# PWR_1117.net
KiCad netlist of a schematic drawn in Altium Designer
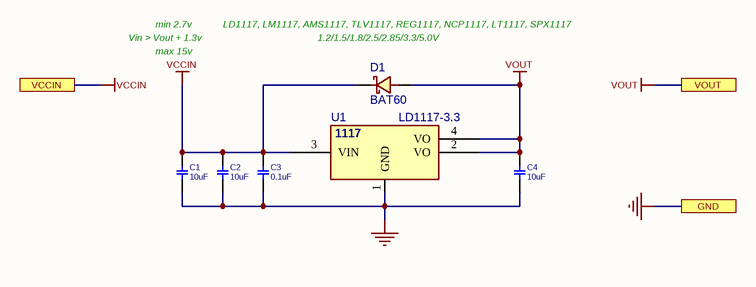
[diagram p0: PWR_1117.SchDoc]

(export (version "E")
  (design (tool "Eeschema 10.0.6"))
  (components
    (comp (ref "C1")
      (value "10uF")
      (footprint "C0805")
      (description "CAP, MLCC, -F, -V, MATERIAL, -%, 1206")
      (fields (field (name "MANF_P#") "MANF_PART#"))
      (libsource (lib "passive_smd") (part "CAP_SMD_MLCC_1206"))
    )
    (comp (ref "C2")
      (value "10uF")
      (footprint "C0805")
      (description "CAP, MLCC, -F, -V, MATERIAL, -%, 1206")
      (fields (field (name "MANF_P#") "MANF_PART#"))
      (libsource (lib "passive_smd") (part "CAP_SMD_MLCC_1206"))
    )
    (comp (ref "C3")
      (value "0.1uF")
      (footprint "C0603")
      (description "CAP, MLCC, -F, -V, MATERIAL, -%, 0805")
      (fields (field (name "MANF_P#") "MANF_PART#"))
      (libsource (lib "passive_smd") (part "CAP_SMD_MLCC_0805"))
    )
    (comp (ref "C4")
      (value "10uF")
      (footprint "C0805")
      (description "CAP, MLCC, -F, -V, MATERIAL, -%, 1206")
      (fields (field (name "MANF_P#") "MANF_PART#"))
      (libsource (lib "passive_smd") (part "CAP_SMD_MLCC_1206"))
    )
    (comp (ref "D1")
      (value "BAT60")
      (footprint "D_SOD323")
      (description "DIODE, SCHOTTKY, 10V, 3A, 0.3Vf")
      (fields (field (name "MANF") "Infineon") (field (name "MANF_P#") "BAT60AE6327HTSA1"))
      (libsource (lib "diode") (part "DIODE_SMD_SCHOTTKY_BAT60"))
    )
    (comp (ref "U1")
      (value "LD1117-3.3")
      (footprint "SOT223_4")
      (description "REG, Linear, LDO1V, 0.8A, SOT-223")
      (fields
        (field (name "MANF_P#") "LD1117, LM1117, AMS1117, TLV1117, REG1117, NCP1117, LT1117, SPX1117")
        (field (name "MANF") "TI, ON, ST")
      )
      (libsource (lib "pwr_reg_linear_1117") (part "VREG_1117_SOT223"))
    )
  )
  (nets
    (net (code "1") (name "GND") (class "Default")
      (node (ref "C1") (pin "2") (pinfunction "2_2") (pintype "passive"))
      (node (ref "C2") (pin "2") (pinfunction "2_2") (pintype "passive"))
      (node (ref "C3") (pin "1") (pinfunction "1_1") (pintype "passive"))
      (node (ref "C4") (pin "2") (pinfunction "2_2") (pintype "passive"))
      (node (ref "U1") (pin "1") (pinfunction "GND_1") (pintype "passive"))
    )
    (net (code "2") (name "VCCIN") (class "Default")
      (node (ref "C1") (pin "1") (pinfunction "1_1") (pintype "passive"))
      (node (ref "C2") (pin "1") (pinfunction "1_1") (pintype "passive"))
      (node (ref "C3") (pin "2") (pinfunction "2_2") (pintype "passive"))
      (node (ref "D1") (pin "2") (pinfunction "2_2") (pintype "passive"))
      (node (ref "U1") (pin "3") (pinfunction "VIN_3") (pintype "passive"))
    )
    (net (code "3") (name "VOUT") (class "Default")
      (node (ref "C4") (pin "1") (pinfunction "1_1") (pintype "passive"))
      (node (ref "D1") (pin "1") (pinfunction "1_1") (pintype "passive"))
      (node (ref "U1") (pin "2") (pinfunction "VO_2") (pintype "passive"))
      (node (ref "U1") (pin "4") (pinfunction "VO_4") (pintype "passive"))
    )
  )
)
